# TNY275_BASE_1059.net
KiCad netlist of a schematic drawn in Altium Designer
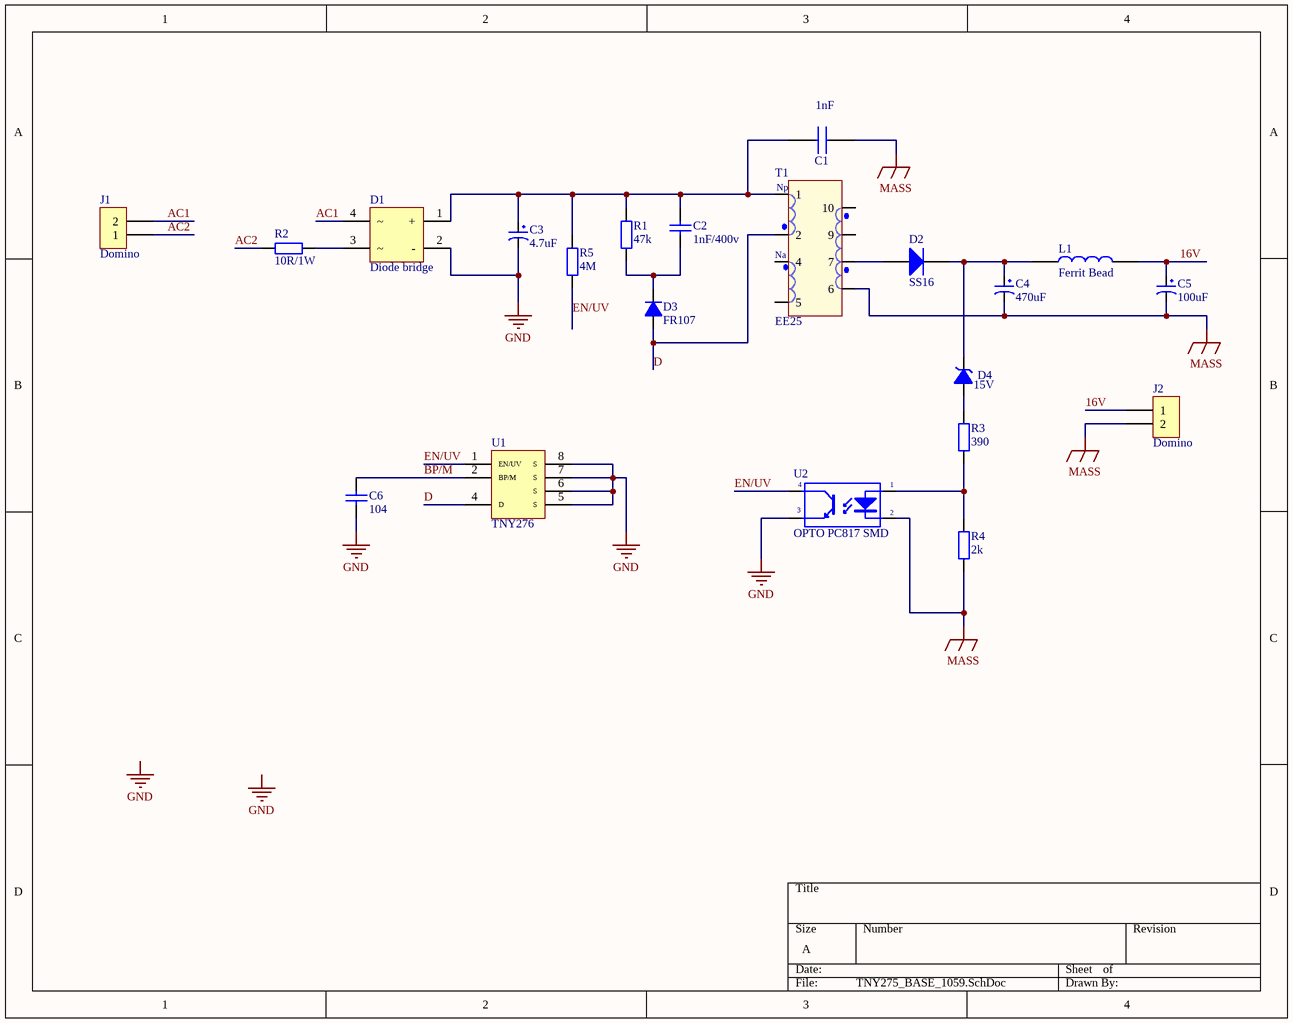
[diagram p0: TNY275_BASE_1059.SchDoc]

(export (version "E")
  (design (tool "Eeschema 10.0.6"))
  (components
    (comp (ref "C1")
      (value "1nF")
      (footprint "toan:Tenta capacitor")
      (description "...nF +/-10% 275VAC 15 Through Hole Suppression Capacitors")
      (fields (field (name "MANUFACTURER_PART_NUMBER") "MEX104K275A"))
      (libsource (lib "Tenta capacitor") (part "Tenta capacitor"))
    )
    (comp (ref "C2")
      (value "1nF/400v")
      (footprint "tu tantalum dip5.08")
      (description "tụ cao áp Cắm")
      (libsource (lib "Altium_Lib_by_KhueNguyenCreator") (part "Tu tantalum 10nF DIP5.08"))
    )
    (comp (ref "C3")
      (value "4.7uF")
      (footprint "tu hoa 8mm")
      (description "Cắm")
      (libsource (lib "Altium_Lib_by_KhueNguyenCreator") (part "Tu Hoa 4.7uF 400V 8x12"))
    )
    (comp (ref "C4")
      (value "470uF")
      (footprint "tu hoa 8mm")
      (description "Cắm")
      (libsource (lib "Altium_Lib_by_KhueNguyenCreator") (part "Tu Hoa 470uF 25V 8x13"))
    )
    (comp (ref "C5")
      (value "100uF")
      (footprint "tu hoa 5mm")
      (description "Cắm")
      (libsource (lib "Altium_Lib_by_KhueNguyenCreator") (part "Tu Hoa 100uF 25V 6x11"))
    )
    (comp (ref "C6")
      (value "104")
      (footprint "tu 0805")
      (description "Dán")
      (libsource (lib "Altium_Lib_by_KhueNguyenCreator") (part "Tu 0805 104 50V 10%"))
    )
    (comp (ref "D1")
      (value "Diode bridge")
      (footprint "DS207S:DS207S")
      (description "Diode cau 2A 1000V")
      (libsource (lib "DS207S") (part "DS207S"))
    )
    (comp (ref "D2")
      (value "SS16")
      (footprint "DIODE SMA")
      (description "Dán")
      (libsource (lib "Altium_Lib_by_KhueNguyenCreator") (part "Diode SS14 ( 1N5819)"))
    )
    (comp (ref "D3")
      (value "FR107")
      (footprint "DIODE 2A")
      (description "Cắm")
      (libsource (lib "Altium_Lib_by_KhueNguyenCreator") (part "Diode FR207"))
    )
    (comp (ref "D4")
      (value "15V")
      (footprint "DZ1A")
      (description "Diode Zenner")
      (libsource (lib "syhaunguyen") (part "DZ"))
    )
    (comp (ref "J1")
      (value "Domino")
      (footprint "Domino:Domino")
      (description "Domino 5.04mm")
      (libsource (lib "") (part "Domino_1"))
    )
    (comp (ref "J2")
      (value "Domino")
      (footprint "Domino:Domino")
      (description "Domino 5.04mm")
      (libsource (lib "Domino") (part "Domino"))
    )
    (comp (ref "L1")
      (value "Ferrit Bead")
      (footprint "Cuon Cam:CUON CAM")
      (description "Cuộn lọc RH3.5x9x0.8 Cắm")
      (libsource (lib "Altium_Lib_by_KhueNguyenCreator") (part "CUON CAM 470uH DIP"))
    )
    (comp (ref "R1")
      (value "47k")
      (footprint "tro smd 0805")
      (description "Dán")
      (libsource (lib "Altium_Lib_by_KhueNguyenCreator") (part "Tro 0805 5% 47k"))
    )
    (comp (ref "R2")
      (value "10R/1W")
      (footprint "tro vach 1w")
      (description "Cắm")
      (libsource (lib "Altium_Lib_by_KhueNguyenCreator") (part "Tro Vach 1W 5% 3.3R"))
    )
    (comp (ref "R3")
      (value "390")
      (footprint "tro smd 0805")
      (description "Dán")
      (libsource (lib "Altium_Lib_by_KhueNguyenCreator") (part "Tro 0805 5% 2.2k"))
    )
    (comp (ref "R4")
      (value "2k")
      (footprint "tro smd 0805")
      (description "Dán")
      (libsource (lib "Altium_Lib_by_KhueNguyenCreator") (part "Tro 0805 5% 220R"))
    )
    (comp (ref "R5")
      (value "4M")
      (footprint "tro smd 0805")
      (description "Dán")
      (libsource (lib "Altium_Lib_by_KhueNguyenCreator") (part "Tro 0805 5% 47k"))
    )
    (comp (ref "T1")
      (value "EE25")
      (footprint "toan:EE25_0.5")
      (description "EE25 10PIN")
      (libsource (lib "EE25") (part "EE25"))
    )
    (comp (ref "U1")
      (value "TNY276")
      (footprint "TNY27X DIP:PCBComponent_1")
      (description "TNY274-280\r\nTinySwitch-III Family - DIP/PDIP-8C")
      (libsource (lib "TNY27X-DIP") (part "TNY276"))
    )
    (comp (ref "U2")
      (value "OPTO PC817 SMD")
      (footprint "SOP4")
      (description "Single Opto")
      (libsource (lib "Altium_Lib_by_KhueNguyenCreator") (part "OPTO PC817 SMD"))
    )
  )
  (nets
    (net (code "1") (name "/16V") (class "Default")
      (node (ref "C5") (pin "1") (pinfunction "1_1") (pintype "passive"))
      (node (ref "J2") (pin "1") (pinfunction "1_1") (pintype "passive"))
      (node (ref "L1") (pin "2") (pinfunction "2_2") (pintype "passive"))
    )
    (net (code "2") (name "/AC1") (class "Default")
      (node (ref "D1") (pin "4") (pinfunction "~_4") (pintype "passive"))
      (node (ref "J1") (pin "2") (pinfunction "2_2") (pintype "passive"))
    )
    (net (code "3") (name "/AC2") (class "Default")
      (node (ref "J1") (pin "1") (pinfunction "1_1") (pintype "passive"))
      (node (ref "R2") (pin "1") (pinfunction "1_1") (pintype "passive"))
    )
    (net (code "4") (name "/BP{slash}M") (class "Default")
      (node (ref "C6") (pin "1") (pinfunction "1_1") (pintype "passive"))
      (node (ref "U1") (pin "2") (pinfunction "BP/M_2") (pintype "passive"))
    )
    (net (code "5") (name "/D") (class "Default")
      (node (ref "D3") (pin "1") (pinfunction "A_1") (pintype "passive"))
      (node (ref "T1") (pin "2") (pinfunction "2_2") (pintype "passive"))
      (node (ref "U1") (pin "4") (pinfunction "D_4") (pintype "passive"))
    )
    (net (code "6") (name "/EN{slash}UV") (class "Default")
      (node (ref "R5") (pin "1") (pinfunction "1_1") (pintype "passive"))
      (node (ref "U1") (pin "1") (pinfunction "EN/UV_1") (pintype "passive"))
      (node (ref "U2") (pin "4") (pinfunction "C_4") (pintype "passive"))
    )
    (net (code "7") (name "GND") (class "Default")
      (node (ref "C3") (pin "2") (pinfunction "2_2") (pintype "passive"))
      (node (ref "C6") (pin "2") (pinfunction "2_2") (pintype "passive"))
      (node (ref "D1") (pin "2") (pinfunction "-_2") (pintype "passive"))
      (node (ref "U1") (pin "5") (pinfunction "S_5") (pintype "passive"))
      (node (ref "U1") (pin "6") (pinfunction "S_6") (pintype "passive"))
      (node (ref "U1") (pin "7") (pinfunction "S_7") (pintype "passive"))
      (node (ref "U1") (pin "8") (pinfunction "S_8") (pintype "passive"))
      (node (ref "U2") (pin "3") (pinfunction "E_3") (pintype "passive"))
    )
    (net (code "8") (name "MASS") (class "Default")
      (node (ref "C1") (pin "2") (pinfunction "2_2") (pintype "passive"))
      (node (ref "C4") (pin "2") (pinfunction "2_2") (pintype "passive"))
      (node (ref "C5") (pin "2") (pinfunction "2_2") (pintype "passive"))
      (node (ref "J2") (pin "2") (pinfunction "2_2") (pintype "passive"))
      (node (ref "R4") (pin "1") (pinfunction "1_1") (pintype "passive"))
      (node (ref "T1") (pin "6") (pinfunction "6_6") (pintype "passive"))
      (node (ref "U2") (pin "2") (pinfunction "K_2") (pintype "passive"))
    )
    (net (code "9") (name "Net-(D1-+)") (class "Default")
      (node (ref "C1") (pin "1") (pinfunction "1_1") (pintype "passive"))
      (node (ref "C2") (pin "1") (pinfunction "1_1") (pintype "passive"))
      (node (ref "C3") (pin "1") (pinfunction "1_1") (pintype "passive"))
      (node (ref "D1") (pin "1") (pinfunction "+_1") (pintype "passive"))
      (node (ref "R1") (pin "2") (pinfunction "2_2") (pintype "passive"))
      (node (ref "R5") (pin "2") (pinfunction "2_2") (pintype "passive"))
      (node (ref "T1") (pin "1") (pinfunction "1_1") (pintype "passive"))
    )
    (net (code "10") (name "Net-(D1-~-Pad3)") (class "Default")
      (node (ref "D1") (pin "3") (pinfunction "~_3") (pintype "passive"))
      (node (ref "R2") (pin "2") (pinfunction "2_2") (pintype "passive"))
    )
    (net (code "11") (name "Net-(D2-A)") (class "Default")
      (node (ref "D2") (pin "1") (pinfunction "A_1") (pintype "passive"))
      (node (ref "T1") (pin "7") (pinfunction "7_7") (pintype "passive"))
    )
    (net (code "12") (name "Net-(D2-K)") (class "Default")
      (node (ref "C4") (pin "1") (pinfunction "1_1") (pintype "passive"))
      (node (ref "D2") (pin "2") (pinfunction "K_2") (pintype "passive"))
      (node (ref "D4") (pin "2") (pinfunction "K_2") (pintype "passive"))
      (node (ref "L1") (pin "1") (pinfunction "1_1") (pintype "passive"))
    )
    (net (code "13") (name "Net-(D3-K)") (class "Default")
      (node (ref "C2") (pin "2") (pinfunction "2_2") (pintype "passive"))
      (node (ref "D3") (pin "2") (pinfunction "K_2") (pintype "passive"))
      (node (ref "R1") (pin "1") (pinfunction "1_1") (pintype "passive"))
    )
    (net (code "14") (name "Net-(D4-A)") (class "Default")
      (node (ref "D4") (pin "1") (pinfunction "A_1") (pintype "passive"))
      (node (ref "R3") (pin "2") (pinfunction "2_2") (pintype "passive"))
    )
    (net (code "15") (name "Net-(U2-A)") (class "Default")
      (node (ref "R3") (pin "1") (pinfunction "1_1") (pintype "passive"))
      (node (ref "R4") (pin "2") (pinfunction "2_2") (pintype "passive"))
      (node (ref "U2") (pin "1") (pinfunction "A_1") (pintype "passive"))
    )
    (net (code "16") (name "unconnected-(T1-Pad4)") (class "Default")
      (node (ref "T1") (pin "4") (pinfunction "4_4") (pintype "passive"))
    )
    (net (code "17") (name "unconnected-(T1-Pad5)") (class "Default")
      (node (ref "T1") (pin "5") (pinfunction "5_5") (pintype "passive"))
    )
    (net (code "18") (name "unconnected-(T1-Pad9)") (class "Default")
      (node (ref "T1") (pin "9") (pinfunction "9_9") (pintype "passive"))
    )
    (net (code "19") (name "unconnected-(T1-Pad10)") (class "Default")
      (node (ref "T1") (pin "10") (pinfunction "10_10") (pintype "passive"))
    )
  )
)
